# Power.net
KiCad netlist of a schematic drawn in Altium Designer
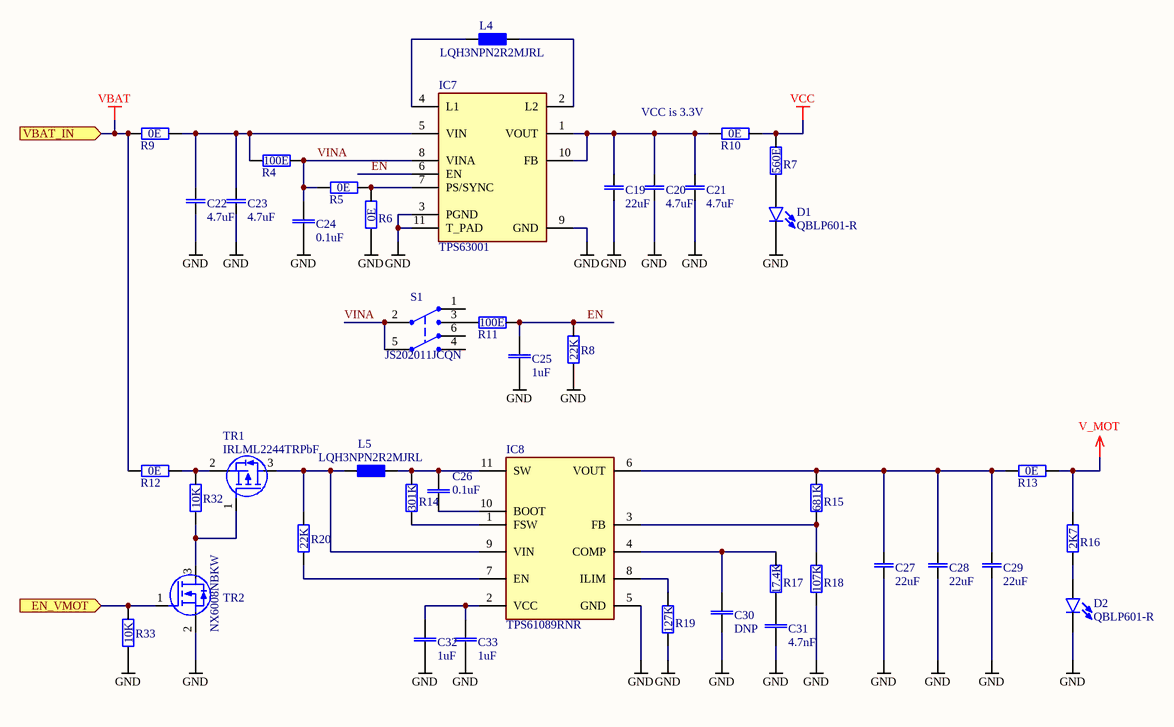
[diagram p0: Power.SchDoc]

(export (version "E")
  (design (tool "Eeschema 10.0.6"))
  (components
    (comp (ref "C19")
      (value "22uF")
      (footprint "0805")
      (fields (field (name "PART NUMBER") "000095") (field (name "MANUFACTURER") "Murata Electronics"))
      (libsource (lib "TychosLibrary") (part "Capacitor"))
    )
    (comp (ref "C20")
      (value "4.7uF")
      (footprint "0805")
      (fields (field (name "PART NUMBER") "000090") (field (name "MANUFACTURER") "Samsung Electro-Mechanics"))
      (libsource (lib "TychosLibrary") (part "Capacitor"))
    )
    (comp (ref "C21")
      (value "4.7uF")
      (footprint "0805")
      (fields (field (name "PART NUMBER") "000090") (field (name "MANUFACTURER") "Samsung Electro-Mechanics"))
      (libsource (lib "TychosLibrary") (part "Capacitor"))
    )
    (comp (ref "C22")
      (value "4.7uF")
      (footprint "0805")
      (fields (field (name "PART NUMBER") "000090") (field (name "MANUFACTURER") "Samsung Electro-Mechanics"))
      (libsource (lib "TychosLibrary") (part "Capacitor"))
    )
    (comp (ref "C23")
      (value "4.7uF")
      (footprint "0805")
      (fields (field (name "PART NUMBER") "000090") (field (name "MANUFACTURER") "Samsung Electro-Mechanics"))
      (libsource (lib "TychosLibrary") (part "Capacitor"))
    )
    (comp (ref "C24")
      (value "0.1uF")
      (footprint "CAP0402")
      (fields (field (name "MANUFACTURER") "Samsung Electro-Mechanics"))
      (libsource (lib "Schematic") (part "CAP_0402"))
    )
    (comp (ref "C25")
      (value "1uF")
      (footprint "CAP0402")
      (fields (field (name "MANUFACTURER") "Samsung Electro-Mechanics"))
      (libsource (lib "Schematic") (part "CAP_0402"))
    )
    (comp (ref "C26")
      (value "0.1uF")
      (footprint "CAP0402")
      (fields (field (name "MANUFACTURER") "Samsung Electro-Mechanics"))
      (libsource (lib "Schematic") (part "CAP_0402"))
    )
    (comp (ref "C27")
      (value "22uF")
      (footprint "0805")
      (fields (field (name "PART NUMBER") "000095") (field (name "MANUFACTURER") "Murata Electronics"))
      (libsource (lib "TychosLibrary") (part "Capacitor"))
    )
    (comp (ref "C28")
      (value "22uF")
      (footprint "0805")
      (fields (field (name "PART NUMBER") "000095") (field (name "MANUFACTURER") "Murata Electronics"))
      (libsource (lib "TychosLibrary") (part "Capacitor"))
    )
    (comp (ref "C29")
      (value "22uF")
      (footprint "0805")
      (fields (field (name "PART NUMBER") "000095") (field (name "MANUFACTURER") "Murata Electronics"))
      (libsource (lib "TychosLibrary") (part "Capacitor"))
    )
    (comp (ref "C30") (value "DNP") (footprint "CAP0402") (libsource (lib "Schematic") (part "CAP_0402")))
    (comp (ref "C31")
      (value "4.7nF")
      (footprint "CAP0402")
      (fields (field (name "MANUFACTURER") "Samsung Electro-Mechanics"))
      (libsource (lib "Schematic") (part "CAP_0402"))
    )
    (comp (ref "C32")
      (value "1uF")
      (footprint "CAP0402")
      (fields (field (name "MANUFACTURER") "Samsung Electro-Mechanics"))
      (libsource (lib "Schematic") (part "CAP_0402"))
    )
    (comp (ref "C33")
      (value "1uF")
      (footprint "CAP0402")
      (fields (field (name "MANUFACTURER") "Samsung Electro-Mechanics"))
      (libsource (lib "Schematic") (part "CAP_0402"))
    )
    (comp (ref "D1")
      (value "QBLP601-R")
      (footprint "LED0603")
      (fields (field (name "MANUFACTURER") "QT Brightek (QTB)"))
      (libsource (lib "Schematic") (part "QBLP601-R"))
    )
    (comp (ref "D2")
      (value "QBLP601-R")
      (footprint "LED0603")
      (fields (field (name "MANUFACTURER") "QT Brightek (QTB)"))
      (libsource (lib "Schematic") (part "QBLP601-R"))
    )
    (comp (ref "IC7")
      (value "TPS63001")
      (footprint "VSON10(TPS63001)")
      (fields (field (name "MANUFACTURER") "Texas Instruments"))
      (libsource (lib "Schematic") (part "TPS63001"))
    )
    (comp (ref "IC8")
      (value "TPS61089RNR")
      (footprint "VQFN12_HOTROD(TPS61089)")
      (fields (field (name "MANUFACTURER") "Texas Instruments"))
      (libsource (lib "Schematic") (part "TPS61089"))
    )
    (comp (ref "L4")
      (value "LQH3NPN2R2MJRL")
      (footprint "INDP3030X02N")
      (fields (field (name "MANUFACTURER") "Murata Electronics"))
      (libsource (lib "Schematic") (part "LQH3NPN2R2MJRL"))
    )
    (comp (ref "L5")
      (value "LQH3NPN2R2MJRL")
      (footprint "INDP3030X02N")
      (fields (field (name "MANUFACTURER") "Murata Electronics"))
      (libsource (lib "Schematic") (part "LQH3NPN2R2MJRL"))
    )
    (comp (ref "R4")
      (value "100E")
      (footprint "RES0402")
      (fields (field (name "MANUFACTURER") "YAGEO"))
      (libsource (lib "Schematic") (part "RES_0402"))
    )
    (comp (ref "R5")
      (value "0E")
      (footprint "RES0402")
      (fields (field (name "MANUFACTURER") "YAGEO"))
      (libsource (lib "Schematic") (part "RES_0402"))
    )
    (comp (ref "R6")
      (value "0E")
      (footprint "RES0402")
      (fields (field (name "MANUFACTURER") "YAGEO"))
      (libsource (lib "Schematic") (part "RES_0402"))
    )
    (comp (ref "R7")
      (value "560E")
      (footprint "RES0402")
      (fields (field (name "MANUFACTURER") "YAGEO"))
      (libsource (lib "Schematic") (part "RES_0402"))
    )
    (comp (ref "R8")
      (value "22K")
      (footprint "RES0402")
      (fields (field (name "MANUFACTURER") "YAGEO"))
      (libsource (lib "Schematic") (part "RES_0402"))
    )
    (comp (ref "R9")
      (value "0E")
      (footprint "RES0402")
      (fields (field (name "MANUFACTURER") "YAGEO"))
      (libsource (lib "Schematic") (part "RES_0402"))
    )
    (comp (ref "R10")
      (value "0E")
      (footprint "RES0402")
      (fields (field (name "MANUFACTURER") "YAGEO"))
      (libsource (lib "Schematic") (part "RES_0402"))
    )
    (comp (ref "R11")
      (value "100E")
      (footprint "RES0402")
      (fields (field (name "MANUFACTURER") "YAGEO"))
      (libsource (lib "Schematic") (part "RES_0402"))
    )
    (comp (ref "R12")
      (value "0E")
      (footprint "RES0402")
      (fields (field (name "MANUFACTURER") "YAGEO"))
      (libsource (lib "Schematic") (part "RES_0402"))
    )
    (comp (ref "R13")
      (value "0E")
      (footprint "RES0402")
      (fields (field (name "MANUFACTURER") "YAGEO"))
      (libsource (lib "Schematic") (part "RES_0402"))
    )
    (comp (ref "R14")
      (value "301K")
      (footprint "RES0402")
      (fields (field (name "MANUFACTURER") "YAGEO"))
      (libsource (lib "Schematic") (part "RES_0402"))
    )
    (comp (ref "R15")
      (value "681K")
      (footprint "RES0402")
      (fields (field (name "MANUFACTURER") "YAGEO"))
      (libsource (lib "Schematic") (part "RES_0402"))
    )
    (comp (ref "R16")
      (value "2K7")
      (footprint "RES0402")
      (fields (field (name "MANUFACTURER") "YAGEO"))
      (libsource (lib "Schematic") (part "RES_0402"))
    )
    (comp (ref "R17")
      (value "17.4K")
      (footprint "RES0402")
      (fields (field (name "MANUFACTURER") "YAGEO"))
      (libsource (lib "Schematic") (part "RES_0402"))
    )
    (comp (ref "R18")
      (value "107K")
      (footprint "RES0402")
      (fields (field (name "MANUFACTURER") "YAGEO"))
      (libsource (lib "Schematic") (part "RES_0402"))
    )
    (comp (ref "R19")
      (value "127K")
      (footprint "RES0402")
      (fields (field (name "MANUFACTURER") "YAGEO"))
      (libsource (lib "Schematic") (part "RES_0402"))
    )
    (comp (ref "R20")
      (value "22K")
      (footprint "RES0402")
      (fields (field (name "MANUFACTURER") "YAGEO"))
      (libsource (lib "Schematic") (part "RES_0402"))
    )
    (comp (ref "R32")
      (value "10K")
      (footprint "RES0402")
      (fields (field (name "MANUFACTURER") "YAGEO"))
      (libsource (lib "Schematic") (part "RES_0402"))
    )
    (comp (ref "R33")
      (value "10K")
      (footprint "RES0402")
      (fields (field (name "MANUFACTURER") "YAGEO"))
      (libsource (lib "Schematic") (part "RES_0402"))
    )
    (comp (ref "S1")
      (value "JS202011JCQN")
      (footprint "JS202011JCQN")
      (fields (field (name "MANUFACTURER") "C&K"))
      (libsource (lib "Schematic") (part "JS202011JCQN"))
    )
    (comp (ref "TR1")
      (value "IRLML2244TRPbF")
      (footprint "SOT23(IRLM2244T)")
      (fields (field (name "MANUFACTURER") "Infineon Technologies"))
      (libsource (lib "Schematic") (part "IRLML2244TRPbF"))
    )
    (comp (ref "TR2")
      (value "NX6008NBKW")
      (footprint "SOT323/SC-70(NX6008NBKW)")
      (libsource (lib "Schematic") (part "NX6008NBKW"))
    )
  )
  (nets
    (net (code "1") (name "/EN") (class "Default")
      (node (ref "C25") (pin "2") (pinfunction "2_2") (pintype "passive"))
      (node (ref "IC7") (pin "6") (pinfunction "EN_6") (pintype "passive"))
      (node (ref "R11") (pin "2") (pinfunction "2_2") (pintype "passive"))
      (node (ref "R8") (pin "2") (pinfunction "2_2") (pintype "passive"))
    )
    (net (code "2") (name "/EN_VMOT") (class "Default")
      (node (ref "R33") (pin "2") (pinfunction "2_2") (pintype "passive"))
      (node (ref "TR2") (pin "1") (pinfunction "G_1") (pintype "passive"))
    )
    (net (code "3") (name "/VINA") (class "Default")
      (node (ref "C24") (pin "2") (pinfunction "2_2") (pintype "passive"))
      (node (ref "IC7") (pin "8") (pinfunction "VINA_8") (pintype "passive"))
      (node (ref "R4") (pin "2") (pinfunction "2_2") (pintype "passive"))
      (node (ref "R5") (pin "1") (pinfunction "1_1") (pintype "passive"))
      (node (ref "S1") (pin "2") (pinfunction "2_2") (pintype "passive"))
      (node (ref "S1") (pin "5") (pinfunction "5_5") (pintype "passive"))
    )
    (net (code "4") (name "GND") (class "Default")
      (node (ref "C19") (pin "1") (pinfunction "1_1") (pintype "passive"))
      (node (ref "C20") (pin "1") (pinfunction "1_1") (pintype "passive"))
      (node (ref "C21") (pin "1") (pinfunction "1_1") (pintype "passive"))
      (node (ref "C22") (pin "1") (pinfunction "1_1") (pintype "passive"))
      (node (ref "C23") (pin "1") (pinfunction "1_1") (pintype "passive"))
      (node (ref "C24") (pin "1") (pinfunction "1_1") (pintype "passive"))
      (node (ref "C25") (pin "1") (pinfunction "1_1") (pintype "passive"))
      (node (ref "C27") (pin "1") (pinfunction "1_1") (pintype "passive"))
      (node (ref "C28") (pin "1") (pinfunction "1_1") (pintype "passive"))
      (node (ref "C29") (pin "1") (pinfunction "1_1") (pintype "passive"))
      (node (ref "C30") (pin "2") (pinfunction "2_2") (pintype "passive"))
      (node (ref "C31") (pin "2") (pinfunction "2_2") (pintype "passive"))
      (node (ref "C32") (pin "2") (pinfunction "2_2") (pintype "passive"))
      (node (ref "C33") (pin "2") (pinfunction "2_2") (pintype "passive"))
      (node (ref "D1") (pin "2") (pinfunction "2_2") (pintype "passive"))
      (node (ref "D2") (pin "2") (pinfunction "2_2") (pintype "passive"))
      (node (ref "IC7") (pin "11") (pinfunction "T_PAD_11") (pintype "passive"))
      (node (ref "IC7") (pin "3") (pinfunction "PGND_3") (pintype "passive"))
      (node (ref "IC7") (pin "9") (pinfunction "GND_9") (pintype "passive"))
      (node (ref "IC8") (pin "5") (pinfunction "GND_5") (pintype "passive"))
      (node (ref "R18") (pin "1") (pinfunction "1_1") (pintype "passive"))
      (node (ref "R19") (pin "1") (pinfunction "1_1") (pintype "passive"))
      (node (ref "R33") (pin "1") (pinfunction "1_1") (pintype "passive"))
      (node (ref "R6") (pin "1") (pinfunction "1_1") (pintype "passive"))
      (node (ref "R8") (pin "1") (pinfunction "1_1") (pintype "passive"))
      (node (ref "TR2") (pin "2") (pinfunction "S_2") (pintype "passive"))
    )
    (net (code "5") (name "Net-(C31-Pad1)") (class "Default")
      (node (ref "C31") (pin "1") (pinfunction "1_1") (pintype "passive"))
      (node (ref "R17") (pin "1") (pinfunction "1_1") (pintype "passive"))
    )
    (net (code "6") (name "Net-(D1-Pad1)") (class "Default")
      (node (ref "D1") (pin "1") (pinfunction "1_1") (pintype "passive"))
      (node (ref "R7") (pin "1") (pinfunction "1_1") (pintype "passive"))
    )
    (net (code "7") (name "Net-(D2-Pad1)") (class "Default")
      (node (ref "D2") (pin "1") (pinfunction "1_1") (pintype "passive"))
      (node (ref "R16") (pin "1") (pinfunction "1_1") (pintype "passive"))
    )
    (net (code "8") (name "Net-(IC7-FB)") (class "Default")
      (node (ref "C19") (pin "2") (pinfunction "2_2") (pintype "passive"))
      (node (ref "C20") (pin "2") (pinfunction "2_2") (pintype "passive"))
      (node (ref "C21") (pin "2") (pinfunction "2_2") (pintype "passive"))
      (node (ref "IC7") (pin "1") (pinfunction "VOUT_1") (pintype "passive"))
      (node (ref "IC7") (pin "10") (pinfunction "FB_10") (pintype "passive"))
      (node (ref "R10") (pin "1") (pinfunction "1_1") (pintype "passive"))
    )
    (net (code "9") (name "Net-(IC7-L1)") (class "Default")
      (node (ref "IC7") (pin "4") (pinfunction "L1_4") (pintype "passive"))
      (node (ref "L4") (pin "1") (pinfunction "1_1") (pintype "passive"))
    )
    (net (code "10") (name "Net-(IC7-L2)") (class "Default")
      (node (ref "IC7") (pin "2") (pinfunction "L2_2") (pintype "passive"))
      (node (ref "L4") (pin "2") (pinfunction "2_2") (pintype "passive"))
    )
    (net (code "11") (name "Net-(IC7-PS{slash}SYNC)") (class "Default")
      (node (ref "IC7") (pin "7") (pinfunction "PS/SYNC_7") (pintype "passive"))
      (node (ref "R5") (pin "2") (pinfunction "2_2") (pintype "passive"))
      (node (ref "R6") (pin "2") (pinfunction "2_2") (pintype "passive"))
    )
    (net (code "12") (name "Net-(IC7-VIN)") (class "Default")
      (node (ref "C22") (pin "2") (pinfunction "2_2") (pintype "passive"))
      (node (ref "C23") (pin "2") (pinfunction "2_2") (pintype "passive"))
      (node (ref "IC7") (pin "5") (pinfunction "VIN_5") (pintype "passive"))
      (node (ref "R4") (pin "1") (pinfunction "1_1") (pintype "passive"))
      (node (ref "R9") (pin "2") (pinfunction "2_2") (pintype "passive"))
    )
    (net (code "13") (name "Net-(IC8-BOOT)") (class "Default")
      (node (ref "C26") (pin "1") (pinfunction "1_1") (pintype "passive"))
      (node (ref "IC8") (pin "10") (pinfunction "BOOT_10") (pintype "passive"))
    )
    (net (code "14") (name "Net-(IC8-COMP)") (class "Default")
      (node (ref "C30") (pin "1") (pinfunction "1_1") (pintype "passive"))
      (node (ref "IC8") (pin "4") (pinfunction "COMP_4") (pintype "passive"))
      (node (ref "R17") (pin "2") (pinfunction "2_2") (pintype "passive"))
    )
    (net (code "15") (name "Net-(IC8-EN)") (class "Default")
      (node (ref "IC8") (pin "7") (pinfunction "EN_7") (pintype "passive"))
      (node (ref "R20") (pin "1") (pinfunction "1_1") (pintype "passive"))
    )
    (net (code "16") (name "Net-(IC8-FB)") (class "Default")
      (node (ref "IC8") (pin "3") (pinfunction "FB_3") (pintype "passive"))
      (node (ref "R15") (pin "1") (pinfunction "1_1") (pintype "passive"))
      (node (ref "R18") (pin "2") (pinfunction "2_2") (pintype "passive"))
    )
    (net (code "17") (name "Net-(IC8-FSW)") (class "Default")
      (node (ref "IC8") (pin "1") (pinfunction "FSW_1") (pintype "passive"))
      (node (ref "R14") (pin "1") (pinfunction "1_1") (pintype "passive"))
    )
    (net (code "18") (name "Net-(IC8-ILIM)") (class "Default")
      (node (ref "IC8") (pin "8") (pinfunction "ILIM_8") (pintype "passive"))
      (node (ref "R19") (pin "2") (pinfunction "2_2") (pintype "passive"))
    )
    (net (code "19") (name "Net-(IC8-SW)") (class "Default")
      (node (ref "C26") (pin "2") (pinfunction "2_2") (pintype "passive"))
      (node (ref "IC8") (pin "11") (pinfunction "SW_11") (pintype "passive"))
      (node (ref "L5") (pin "2") (pinfunction "2_2") (pintype "passive"))
      (node (ref "R14") (pin "2") (pinfunction "2_2") (pintype "passive"))
    )
    (net (code "20") (name "Net-(IC8-VCC)") (class "Default")
      (node (ref "C32") (pin "1") (pinfunction "1_1") (pintype "passive"))
      (node (ref "C33") (pin "1") (pinfunction "1_1") (pintype "passive"))
      (node (ref "IC8") (pin "2") (pinfunction "VCC_2") (pintype "passive"))
    )
    (net (code "21") (name "Net-(IC8-VIN)") (class "Default")
      (node (ref "IC8") (pin "9") (pinfunction "VIN_9") (pintype "passive"))
      (node (ref "L5") (pin "1") (pinfunction "1_1") (pintype "passive"))
      (node (ref "R20") (pin "2") (pinfunction "2_2") (pintype "passive"))
      (node (ref "TR1") (pin "3") (pinfunction "D_3") (pintype "passive"))
    )
    (net (code "22") (name "Net-(IC8-VOUT)") (class "Default")
      (node (ref "C27") (pin "2") (pinfunction "2_2") (pintype "passive"))
      (node (ref "C28") (pin "2") (pinfunction "2_2") (pintype "passive"))
      (node (ref "C29") (pin "2") (pinfunction "2_2") (pintype "passive"))
      (node (ref "IC8") (pin "6") (pinfunction "VOUT_6") (pintype "passive"))
      (node (ref "R13") (pin "1") (pinfunction "1_1") (pintype "passive"))
      (node (ref "R15") (pin "2") (pinfunction "2_2") (pintype "passive"))
    )
    (net (code "23") (name "Net-(R11-Pad1)") (class "Default")
      (node (ref "R11") (pin "1") (pinfunction "1_1") (pintype "passive"))
      (node (ref "S1") (pin "3") (pinfunction "3_3") (pintype "passive"))
    )
    (net (code "24") (name "Net-(TR1-G)") (class "Default")
      (node (ref "R32") (pin "1") (pinfunction "1_1") (pintype "passive"))
      (node (ref "TR1") (pin "1") (pinfunction "G_1") (pintype "passive"))
      (node (ref "TR2") (pin "3") (pinfunction "D_3") (pintype "passive"))
    )
    (net (code "25") (name "Net-(TR1-S)") (class "Default")
      (node (ref "R12") (pin "2") (pinfunction "2_2") (pintype "passive"))
      (node (ref "R32") (pin "2") (pinfunction "2_2") (pintype "passive"))
      (node (ref "TR1") (pin "2") (pinfunction "S_2") (pintype "passive"))
    )
    (net (code "26") (name "VBAT") (class "Default")
      (node (ref "R12") (pin "1") (pinfunction "1_1") (pintype "passive"))
      (node (ref "R9") (pin "1") (pinfunction "1_1") (pintype "passive"))
    )
    (net (code "27") (name "VCC") (class "Default")
      (node (ref "R10") (pin "2") (pinfunction "2_2") (pintype "passive"))
      (node (ref "R7") (pin "2") (pinfunction "2_2") (pintype "passive"))
    )
    (net (code "28") (name "V_MOT") (class "Default")
      (node (ref "R13") (pin "2") (pinfunction "2_2") (pintype "passive"))
      (node (ref "R16") (pin "2") (pinfunction "2_2") (pintype "passive"))
    )
    (net (code "29") (name "unconnected-(S1-Pad1)") (class "Default")
      (node (ref "S1") (pin "1") (pinfunction "1_1") (pintype "passive"))
    )
    (net (code "30") (name "unconnected-(S1-Pad4)") (class "Default")
      (node (ref "S1") (pin "4") (pinfunction "4_4") (pintype "passive"))
    )
    (net (code "31") (name "unconnected-(S1-Pad6)") (class "Default")
      (node (ref "S1") (pin "6") (pinfunction "6_6") (pintype "passive"))
    )
  )
)
